# SCH_TIMER_2025-06-27.net
KiCad netlist of a schematic drawn in EasyEDA
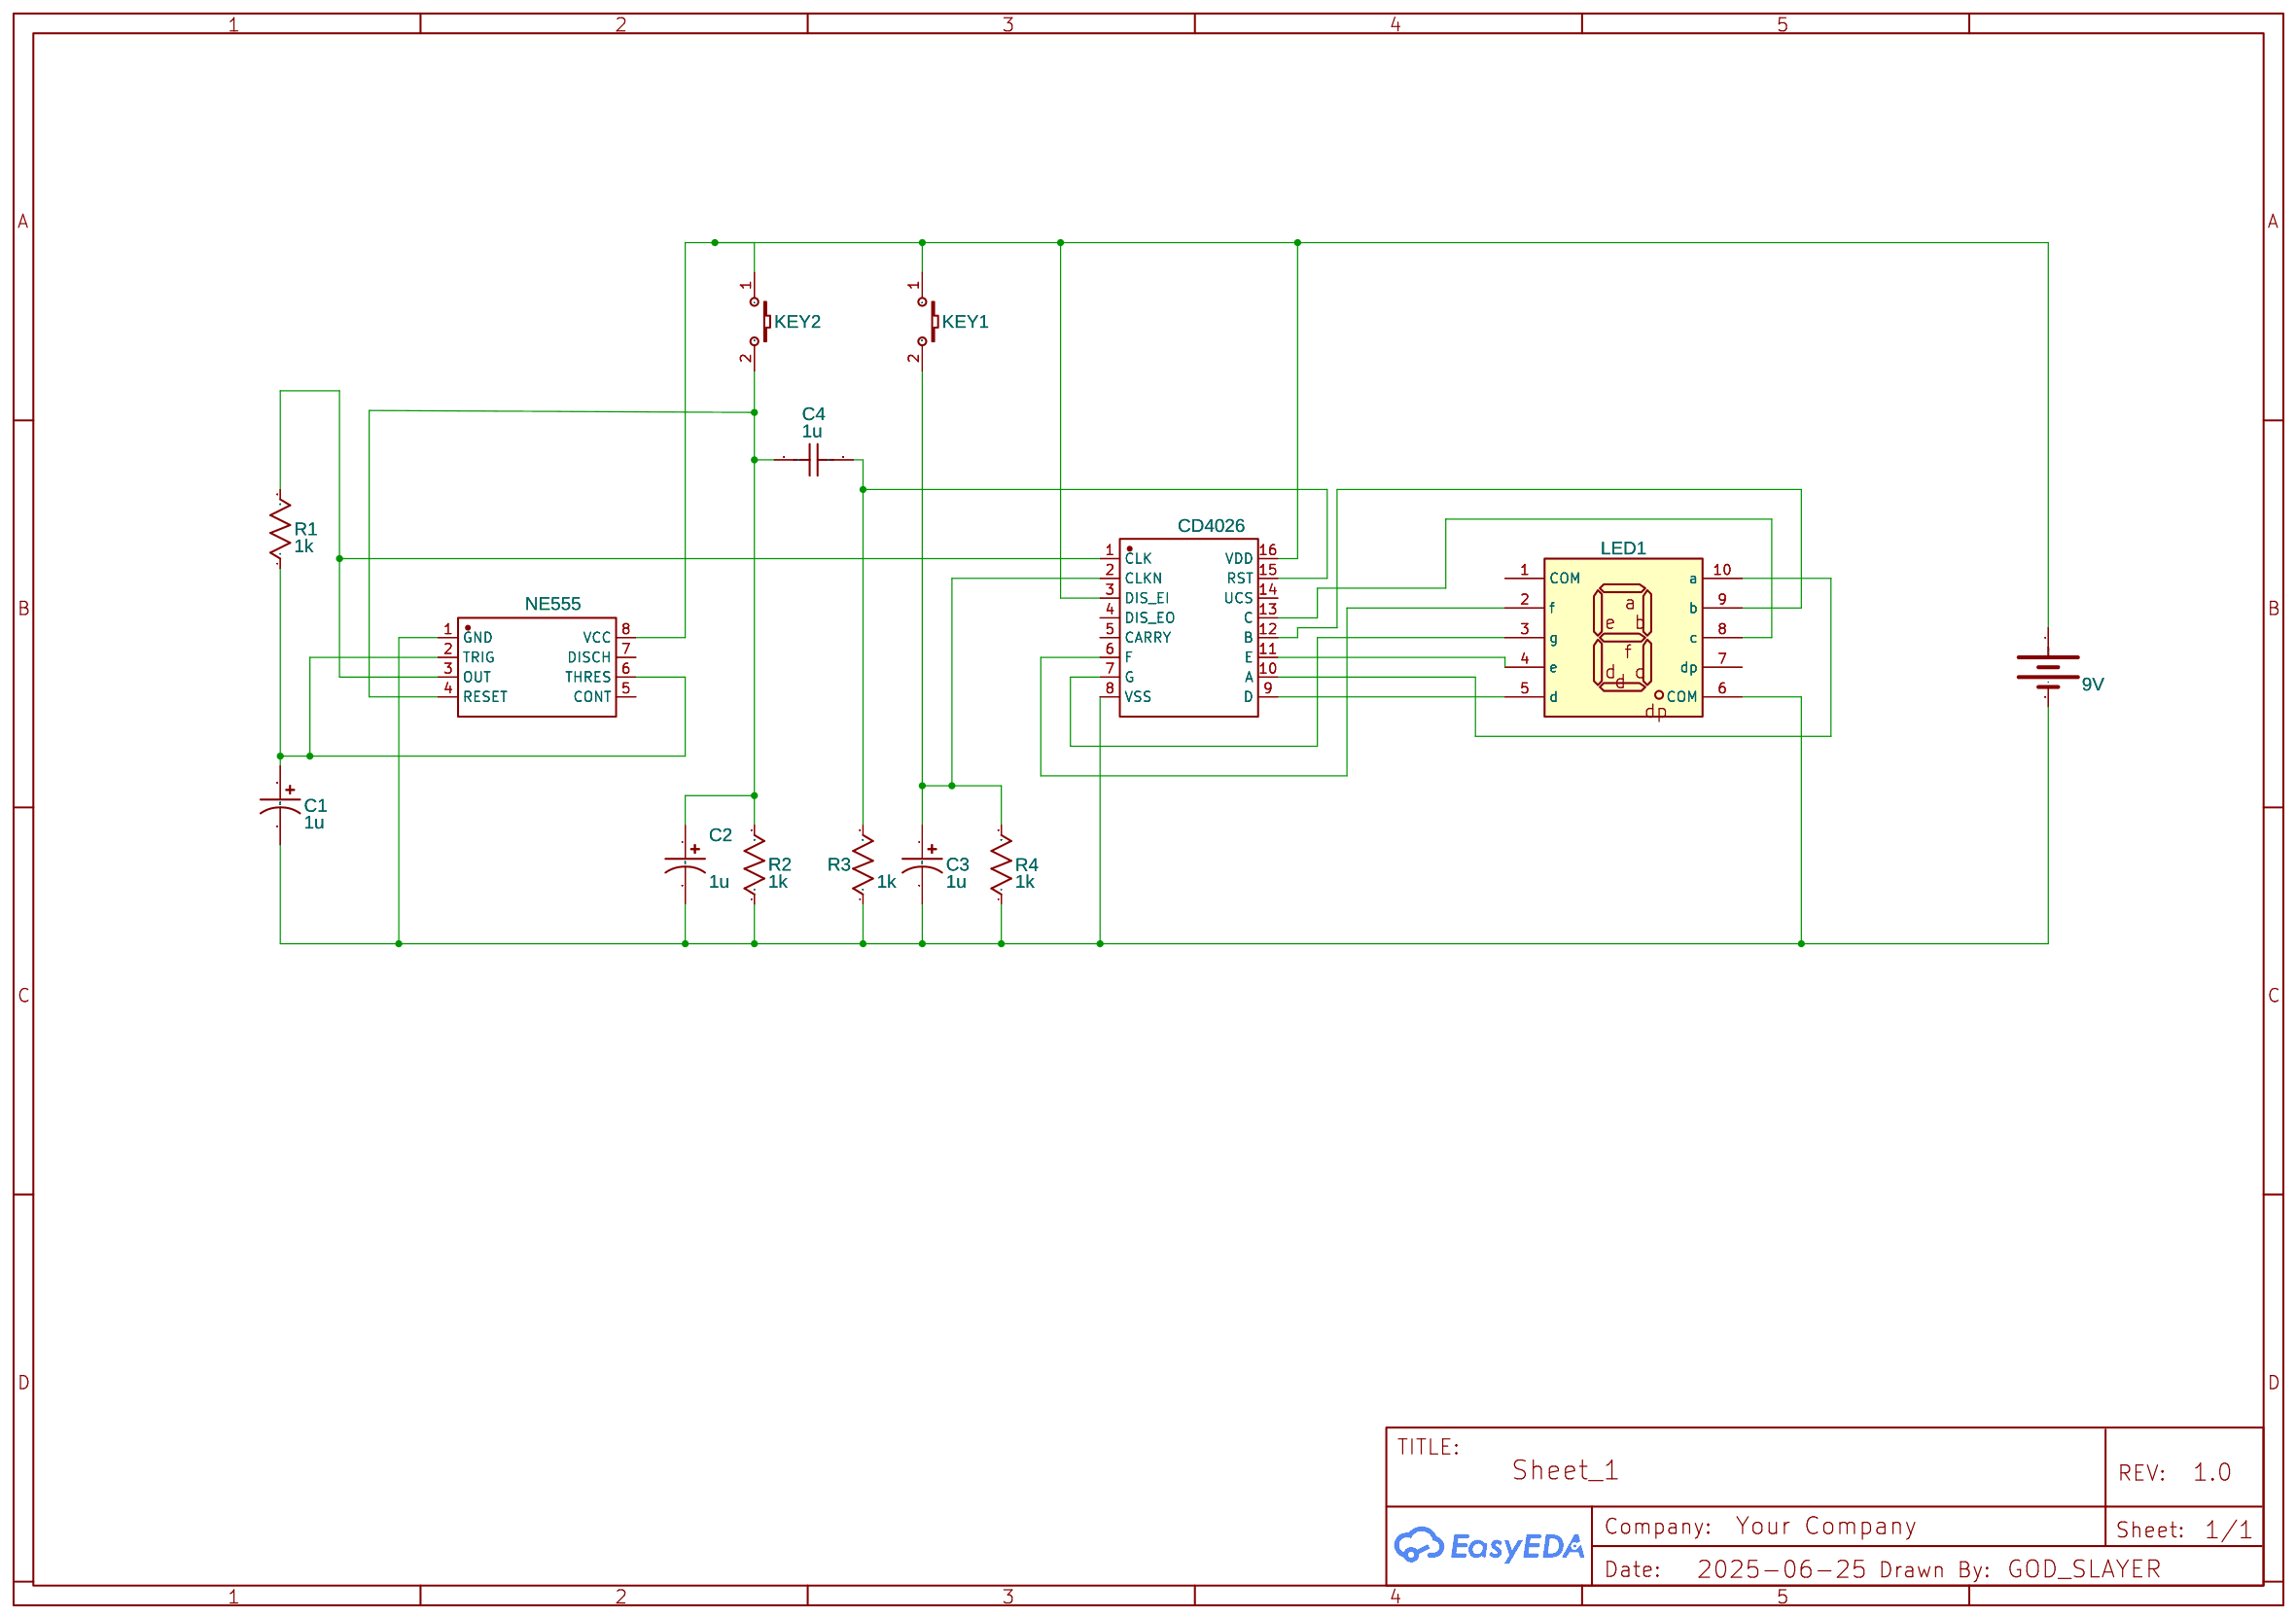
[diagram p0: schematic sheet]

(export (version "E")
  (design (tool "Eeschema 10.0.6"))
  (components
    (comp (ref "BT1")
      (value "9V")
      (fields (field (name "Manufacturer Part") "9V电池铜线扣 铜100mm") (field (name "Manufacturer") "Q&J"))
      (libsource (lib "") (part "9V电池铜线扣 铜100MM"))
    )
    (comp (ref "C1") (value "1u") (libsource (lib "") (part "CE_SMD_D4.0×H5.5_US")))
    (comp (ref "C2") (value "1u") (libsource (lib "") (part "CE_SMD_D4.0×H5.5_US_1")))
    (comp (ref "C3") (value "1u") (libsource (lib "") (part "CE_SMD_D4.0×H5.5_US_1")))
    (comp (ref "C4") (value "1u") (libsource (lib "") (part "C_RAD-0.1_US")))
    (comp (ref "KEY1")
      (value "K2-3.6×6.1_SMD")
      (fields (field (name "Manufacturer Part") "K2-1107ST-A4SW-06"))
      (libsource (lib "") (part "K2-3.6×6.1_SMD"))
    )
    (comp (ref "KEY2")
      (value "K2-3.6×6.1_SMD")
      (fields (field (name "Manufacturer Part") "K2-1107ST-A4SW-06"))
      (libsource (lib "") (part "K2-3.6×6.1_SMD"))
    )
    (comp (ref "LED1")
      (value "FJ3161BH")
      (fields (field (name "Manufacturer") "志浩"))
      (libsource (lib "") (part "FJ3161BH"))
    )
    (comp (ref "R1") (value "1k") (libsource (lib "") (part "R_AXIAL-0.3_US")))
    (comp (ref "R2") (value "1k") (libsource (lib "") (part "R_AXIAL-0.3_US")))
    (comp (ref "R3") (value "1k") (libsource (lib "") (part "R_AXIAL-0.3_US")))
    (comp (ref "R4") (value "1k") (libsource (lib "") (part "R_AXIAL-0.3_US")))
    (comp (ref "U1")
      (value "NE555")
      (fields (field (name "Manufacturer Part") "NE555PE4") (field (name "Manufacturer") "TI(德州仪器)"))
      (libsource (lib "") (part "NE555PE4"))
    )
    (comp (ref "U2")
      (value "CD4026")
      (fields (field (name "Manufacturer Part") "CD4026BE(LX)") (field (name "Manufacturer") "LX(灵星芯微)"))
      (libsource (lib "") (part "CD4026BE(LX)"))
    )
  )
  (nets
    (net (code "1") (name "Net-(BT1-+)") (class "Default")
      (node (ref "BT1") (pin "1") (pinfunction "+_1") (pintype "passive"))
      (node (ref "KEY1") (pin "1") (pinfunction "1_1") (pintype "unspecified"))
      (node (ref "KEY2") (pin "1") (pinfunction "1_1") (pintype "unspecified"))
      (node (ref "U1") (pin "8") (pinfunction "VCC_8") (pintype "unspecified"))
      (node (ref "U2") (pin "16") (pinfunction "VDD_16") (pintype "unspecified"))
      (node (ref "U2") (pin "3") (pinfunction "DIS_EI_3") (pintype "unspecified"))
    )
    (net (code "2") (name "Net-(BT1--)") (class "Default")
      (node (ref "BT1") (pin "2") (pinfunction "-_2") (pintype "passive"))
      (node (ref "C1") (pin "2") (pinfunction "2_2") (pintype "unspecified"))
      (node (ref "C2") (pin "2") (pinfunction "2_2") (pintype "unspecified"))
      (node (ref "C3") (pin "2") (pinfunction "2_2") (pintype "unspecified"))
      (node (ref "LED1") (pin "6") (pinfunction "COM_6") (pintype "input"))
      (node (ref "R2") (pin "1") (pinfunction "1_1") (pintype "unspecified"))
      (node (ref "R3") (pin "1") (pinfunction "1_1") (pintype "unspecified"))
      (node (ref "R4") (pin "1") (pinfunction "1_1") (pintype "unspecified"))
      (node (ref "U1") (pin "1") (pinfunction "GND_1") (pintype "unspecified"))
      (node (ref "U2") (pin "8") (pinfunction "VSS_8") (pintype "unspecified"))
    )
    (net (code "3") (name "Net-(LED1-a)") (class "Default")
      (node (ref "LED1") (pin "10") (pinfunction "a_10") (pintype "input"))
      (node (ref "U2") (pin "10") (pinfunction "A_10") (pintype "unspecified"))
    )
    (net (code "4") (name "Net-(LED1-b)") (class "Default")
      (node (ref "LED1") (pin "9") (pinfunction "b_9") (pintype "input"))
      (node (ref "U2") (pin "12") (pinfunction "B_12") (pintype "unspecified"))
    )
    (net (code "5") (name "Net-(LED1-c)") (class "Default")
      (node (ref "LED1") (pin "8") (pinfunction "c_8") (pintype "input"))
      (node (ref "U2") (pin "13") (pinfunction "C_13") (pintype "unspecified"))
    )
    (net (code "6") (name "Net-(LED1-d)") (class "Default")
      (node (ref "LED1") (pin "5") (pinfunction "d_5") (pintype "input"))
      (node (ref "U2") (pin "9") (pinfunction "D_9") (pintype "unspecified"))
    )
    (net (code "7") (name "Net-(LED1-e)") (class "Default")
      (node (ref "LED1") (pin "4") (pinfunction "e_4") (pintype "input"))
      (node (ref "U2") (pin "11") (pinfunction "E_11") (pintype "unspecified"))
    )
    (net (code "8") (name "Net-(LED1-f)") (class "Default")
      (node (ref "LED1") (pin "2") (pinfunction "f_2") (pintype "input"))
      (node (ref "U2") (pin "6") (pinfunction "F_6") (pintype "unspecified"))
    )
    (net (code "9") (name "Net-(LED1-g)") (class "Default")
      (node (ref "LED1") (pin "3") (pinfunction "g_3") (pintype "input"))
      (node (ref "U2") (pin "7") (pinfunction "G_7") (pintype "unspecified"))
    )
    (net (code "10") (name "Net-(U1-OUT)") (class "Default")
      (node (ref "R1") (pin "2") (pinfunction "2_2") (pintype "unspecified"))
      (node (ref "U1") (pin "3") (pinfunction "OUT_3") (pintype "unspecified"))
      (node (ref "U2") (pin "1") (pinfunction "CLK_1") (pintype "unspecified"))
    )
    (net (code "11") (name "Net-(U1-RESET)") (class "Default")
      (node (ref "C2") (pin "1") (pinfunction "1_1") (pintype "unspecified"))
      (node (ref "C4") (pin "1") (pinfunction "1_1") (pintype "unspecified"))
      (node (ref "KEY2") (pin "2") (pinfunction "2_2") (pintype "unspecified"))
      (node (ref "R2") (pin "2") (pinfunction "2_2") (pintype "unspecified"))
      (node (ref "U1") (pin "4") (pinfunction "RESET_4") (pintype "unspecified"))
    )
    (net (code "12") (name "Net-(U1-THRES)") (class "Default")
      (node (ref "C1") (pin "1") (pinfunction "1_1") (pintype "unspecified"))
      (node (ref "R1") (pin "1") (pinfunction "1_1") (pintype "unspecified"))
      (node (ref "U1") (pin "2") (pinfunction "TRIG_2") (pintype "unspecified"))
      (node (ref "U1") (pin "6") (pinfunction "THRES_6") (pintype "unspecified"))
    )
    (net (code "13") (name "Net-(U2-CLKN)") (class "Default")
      (node (ref "C3") (pin "1") (pinfunction "1_1") (pintype "unspecified"))
      (node (ref "KEY1") (pin "2") (pinfunction "2_2") (pintype "unspecified"))
      (node (ref "R4") (pin "2") (pinfunction "2_2") (pintype "unspecified"))
      (node (ref "U2") (pin "2") (pinfunction "CLKN_2") (pintype "unspecified"))
    )
    (net (code "14") (name "Net-(U2-RST)") (class "Default")
      (node (ref "C4") (pin "2") (pinfunction "2_2") (pintype "unspecified"))
      (node (ref "R3") (pin "2") (pinfunction "2_2") (pintype "unspecified"))
      (node (ref "U2") (pin "15") (pinfunction "RST_15") (pintype "unspecified"))
    )
    (net (code "15") (name "unconnected-(LED1-COM-Pad1)") (class "Default")
      (node (ref "LED1") (pin "1") (pinfunction "COM_1") (pintype "input"))
    )
    (net (code "16") (name "unconnected-(LED1-dp-Pad7)") (class "Default")
      (node (ref "LED1") (pin "7") (pinfunction "dp_7") (pintype "input"))
    )
    (net (code "17") (name "unconnected-(U1-CONT-Pad5)") (class "Default")
      (node (ref "U1") (pin "5") (pinfunction "CONT_5") (pintype "unspecified"))
    )
    (net (code "18") (name "unconnected-(U1-DISCH-Pad7)") (class "Default")
      (node (ref "U1") (pin "7") (pinfunction "DISCH_7") (pintype "unspecified"))
    )
    (net (code "19") (name "unconnected-(U2-CARRY-Pad5)") (class "Default")
      (node (ref "U2") (pin "5") (pinfunction "CARRY_5") (pintype "unspecified"))
    )
    (net (code "20") (name "unconnected-(U2-DIS_EO-Pad4)") (class "Default")
      (node (ref "U2") (pin "4") (pinfunction "DIS_EO_4") (pintype "unspecified"))
    )
    (net (code "21") (name "unconnected-(U2-UCS-Pad14)") (class "Default")
      (node (ref "U2") (pin "14") (pinfunction "UCS_14") (pintype "unspecified"))
    )
  )
)
